# untitled.net
KiCad netlist of a schematic drawn in EAGLE
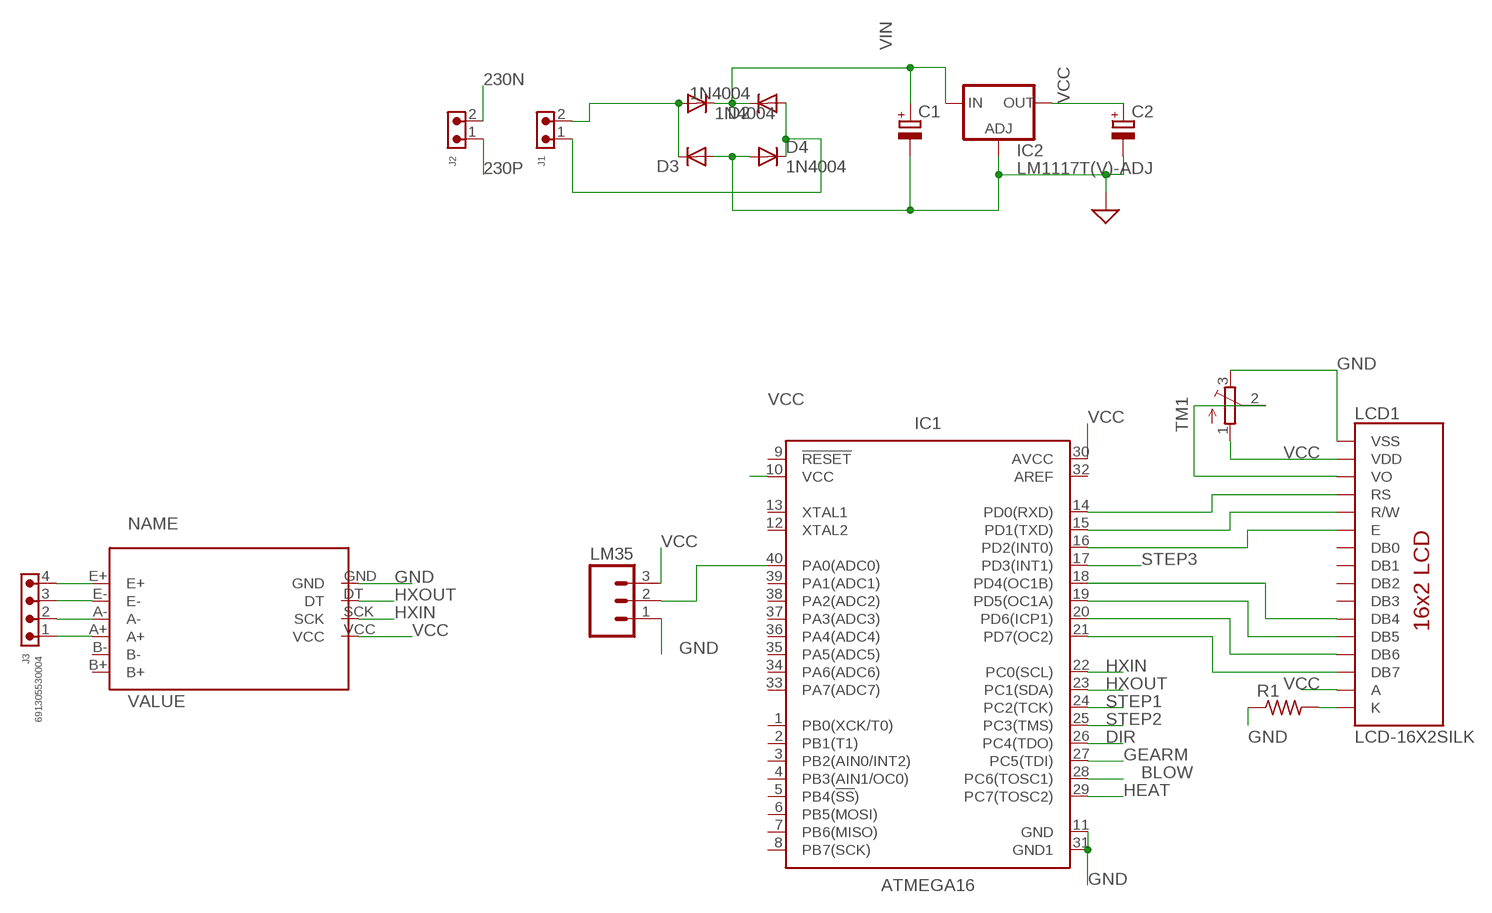
[diagram p0: schematic, sheet 1]

(export (version "E")
  (design (tool "Eeschema 10.0.6"))
  (components
    (comp (ref "C1")
      (value "CPOL-EUE5-10.5")
      (footprint "eagle-import:E5-10,5")
      (libsource (lib "eagle-import") (part "CPOL-EUE5-10.5"))
    )
    (comp (ref "C2")
      (value "CPOL-EUE5-10.5")
      (footprint "eagle-import:E5-10,5")
      (libsource (lib "eagle-import") (part "CPOL-EUE5-10.5"))
    )
    (comp (ref "D1")
      (value "1N4004")
      (footprint "eagle-import:DO41-10")
      (libsource (lib "eagle-import") (part "1N4004"))
    )
    (comp (ref "D2")
      (value "1N4004")
      (footprint "eagle-import:DO41-10")
      (libsource (lib "eagle-import") (part "1N4004"))
    )
    (comp (ref "D3")
      (value "1N4004")
      (footprint "eagle-import:DO41-10")
      (libsource (lib "eagle-import") (part "1N4004"))
    )
    (comp (ref "D4")
      (value "1N4004")
      (footprint "eagle-import:DO41-10")
      (libsource (lib "eagle-import") (part "1N4004"))
    )
    (comp (ref "IC1")
      (value "ATMEGA16")
      (footprint "eagle-import:DIP1587W56P254L5229H482Q40B")
      (fields (field (name "MANUFACTURER") "Microchip Technology") (field (name "MPN") "ATMEGA32-16PU"))
      (libsource (lib "eagle-import") (part "ATMEGA32DIP-16PU_"))
    )
    (comp (ref "IC2")
      (value "LM1117T(V)-ADJ")
      (footprint "eagle-import:TO220V")
      (fields (field (name "MF") "Texas Instruments") (field (name "MPN") "LM1777T-ADJ"))
      (libsource (lib "eagle-import") (part "LM1117?-ADJT(V)"))
    )
    (comp (ref "J1")
      (value "691305530002")
      (footprint "eagle-import:691305530002")
      (libsource (lib "eagle-import") (part "691305530002"))
    )
    (comp (ref "J2")
      (value "691305530002")
      (footprint "eagle-import:691305530002")
      (libsource (lib "eagle-import") (part "691305530002"))
    )
    (comp (ref "J3")
      (value "691305530004")
      (footprint "eagle-import:691305530004")
      (libsource (lib "eagle-import") (part "691305530004"))
    )
    (comp (ref "LCD1")
      (value "LCD-16X2SILK")
      (footprint "eagle-import:LCD-16X2")
      (libsource (lib "eagle-import") (part "LCD-16X2SILK"))
    )
    (comp (ref "LM35")
      (value "M03")
      (footprint "eagle-import:03P")
      (libsource (lib "eagle-import") (part "M03"))
    )
    (comp (ref "R1")
      (value "R-US_0207/9")
      (footprint "eagle-import:0207_9")
      (libsource (lib "eagle-import") (part "R-US_0207/9"))
    )
    (comp (ref "TM1")
      (value "TRIMPOTTC33X")
      (footprint "eagle-import:TC33X")
      (libsource (lib "eagle-import") (part "TRIMPOTTC33X"))
    )
    (comp (ref "U$3")
      (value "HX711A")
      (footprint "eagle-import:HX711")
      (libsource (lib "eagle-import") (part "HX711A"))
    )
  )
  (nets
    (net (code "1") (name "/230N") (class "Default")
      (node (ref "J2") (pin "2") (pinfunction "2_2") (pintype "passive"))
    )
    (net (code "2") (name "/230P") (class "Default")
      (node (ref "J2") (pin "1") (pinfunction "1_1") (pintype "passive"))
    )
    (net (code "3") (name "/BLOW") (class "Default")
      (node (ref "IC1") (pin "28") (pinfunction "PC6(TOSC1)_28") (pintype "bidirectional"))
    )
    (net (code "4") (name "/DIR") (class "Default")
      (node (ref "IC1") (pin "26") (pinfunction "PC4(TDO)_26") (pintype "output"))
    )
    (net (code "5") (name "/GEARM") (class "Default")
      (node (ref "IC1") (pin "27") (pinfunction "PC5(TDI)_27") (pintype "input"))
    )
    (net (code "6") (name "/HEAT") (class "Default")
      (node (ref "IC1") (pin "29") (pinfunction "PC7(TOSC2)_29") (pintype "bidirectional"))
    )
    (net (code "7") (name "/HXIN") (class "Default")
      (node (ref "IC1") (pin "22") (pinfunction "PC0(SCL)_22") (pintype "bidirectional"))
      (node (ref "U$3") (pin "SCK") (pinfunction "SCK_SCK") (pintype "bidirectional"))
    )
    (net (code "8") (name "/HXOUT") (class "Default")
      (node (ref "IC1") (pin "23") (pinfunction "PC1(SDA)_23") (pintype "bidirectional"))
      (node (ref "U$3") (pin "DT") (pinfunction "DT_DT") (pintype "bidirectional"))
    )
    (net (code "9") (name "/STEP1") (class "Default")
      (node (ref "IC1") (pin "24") (pinfunction "PC2(TCK)_24") (pintype "input"))
    )
    (net (code "10") (name "/STEP2") (class "Default")
      (node (ref "IC1") (pin "25") (pinfunction "PC3(TMS)_25") (pintype "input"))
    )
    (net (code "11") (name "/STEP3") (class "Default")
      (node (ref "IC1") (pin "17") (pinfunction "PD3(INT1)_17") (pintype "bidirectional"))
    )
    (net (code "12") (name "/VCC") (class "Default")
      (node (ref "C2") (pin "+") (pinfunction "+_+") (pintype "passive"))
      (node (ref "IC1") (pin "10") (pinfunction "VCC_10") (pintype "power_in"))
      (node (ref "IC1") (pin "30") (pinfunction "AVCC_30") (pintype "power_in"))
      (node (ref "IC2") (pin "2") (pinfunction "OUT_2") (pintype "passive"))
      (node (ref "LCD1") (pin "15") (pinfunction "A_15") (pintype "power_in"))
      (node (ref "LCD1") (pin "2") (pinfunction "VDD_2") (pintype "power_in"))
      (node (ref "LM35") (pin "3") (pinfunction "3_3") (pintype "passive"))
      (node (ref "TM1") (pin "1") (pinfunction "A_1") (pintype "passive"))
      (node (ref "U$3") (pin "VCC") (pinfunction "VCC_VCC") (pintype "bidirectional"))
    )
    (net (code "13") (name "/VIN") (class "Default")
      (node (ref "C1") (pin "+") (pinfunction "+_+") (pintype "passive"))
      (node (ref "D1") (pin "C") (pinfunction "C_C") (pintype "passive"))
      (node (ref "D2") (pin "C") (pinfunction "C_C") (pintype "passive"))
      (node (ref "IC2") (pin "3") (pinfunction "IN_3") (pintype "input"))
    )
    (net (code "14") (name "Net-(D1-PadA)") (class "Default")
      (node (ref "D1") (pin "A") (pinfunction "A_A") (pintype "passive"))
      (node (ref "D3") (pin "C") (pinfunction "C_C") (pintype "passive"))
      (node (ref "J1") (pin "2") (pinfunction "2_2") (pintype "passive"))
    )
    (net (code "15") (name "Net-(D2-PadA)") (class "Default")
      (node (ref "D2") (pin "A") (pinfunction "A_A") (pintype "passive"))
      (node (ref "D4") (pin "C") (pinfunction "C_C") (pintype "passive"))
      (node (ref "J1") (pin "1") (pinfunction "1_1") (pintype "passive"))
    )
    (net (code "16") (name "Net-(IC1-PA0(ADC0))") (class "Default")
      (node (ref "IC1") (pin "40") (pinfunction "PA0(ADC0)_40") (pintype "bidirectional"))
      (node (ref "LM35") (pin "2") (pinfunction "2_2") (pintype "passive"))
    )
    (net (code "17") (name "Net-(IC1-PD0(RXD))") (class "Default")
      (node (ref "IC1") (pin "14") (pinfunction "PD0(RXD)_14") (pintype "bidirectional"))
      (node (ref "LCD1") (pin "4") (pinfunction "RS_4") (pintype "input"))
    )
    (net (code "18") (name "Net-(IC1-PD1(TXD))") (class "Default")
      (node (ref "IC1") (pin "15") (pinfunction "PD1(TXD)_15") (pintype "bidirectional"))
      (node (ref "LCD1") (pin "5") (pinfunction "R/W_5") (pintype "input"))
    )
    (net (code "19") (name "Net-(IC1-PD2(INT0))") (class "Default")
      (node (ref "IC1") (pin "16") (pinfunction "PD2(INT0)_16") (pintype "bidirectional"))
      (node (ref "LCD1") (pin "6") (pinfunction "E_6") (pintype "input"))
    )
    (net (code "20") (name "Net-(IC1-PD4(OC1B))") (class "Default")
      (node (ref "IC1") (pin "18") (pinfunction "PD4(OC1B)_18") (pintype "bidirectional"))
      (node (ref "LCD1") (pin "11") (pinfunction "DB4_11") (pintype "bidirectional"))
    )
    (net (code "21") (name "Net-(IC1-PD5(OC1A))") (class "Default")
      (node (ref "IC1") (pin "19") (pinfunction "PD5(OC1A)_19") (pintype "bidirectional"))
      (node (ref "LCD1") (pin "12") (pinfunction "DB5_12") (pintype "bidirectional"))
    )
    (net (code "22") (name "Net-(IC1-PD6(ICP1))") (class "Default")
      (node (ref "IC1") (pin "20") (pinfunction "PD6(ICP1)_20") (pintype "bidirectional"))
      (node (ref "LCD1") (pin "13") (pinfunction "DB6_13") (pintype "bidirectional"))
    )
    (net (code "23") (name "Net-(IC1-PD7(OC2))") (class "Default")
      (node (ref "IC1") (pin "21") (pinfunction "PD7(OC2)_21") (pintype "bidirectional"))
      (node (ref "LCD1") (pin "14") (pinfunction "DB7_14") (pintype "bidirectional"))
    )
    (net (code "24") (name "Net-(J3-Pad1)") (class "Default")
      (node (ref "J3") (pin "1") (pinfunction "1_1") (pintype "passive"))
      (node (ref "U$3") (pin "A+") (pinfunction "A+_A+") (pintype "bidirectional"))
    )
    (net (code "25") (name "Net-(J3-Pad2)") (class "Default")
      (node (ref "J3") (pin "2") (pinfunction "2_2") (pintype "passive"))
      (node (ref "U$3") (pin "A-") (pinfunction "A-_A-") (pintype "bidirectional"))
    )
    (net (code "26") (name "Net-(J3-Pad3)") (class "Default")
      (node (ref "J3") (pin "3") (pinfunction "3_3") (pintype "passive"))
      (node (ref "U$3") (pin "E-") (pinfunction "E-_E-") (pintype "bidirectional"))
    )
    (net (code "27") (name "Net-(J3-Pad4)") (class "Default")
      (node (ref "J3") (pin "4") (pinfunction "4_4") (pintype "passive"))
      (node (ref "U$3") (pin "E+") (pinfunction "E+_E+") (pintype "bidirectional"))
    )
    (net (code "28") (name "Net-(LCD1-K)") (class "Default")
      (node (ref "LCD1") (pin "16") (pinfunction "K_16") (pintype "power_in"))
      (node (ref "R1") (pin "2") (pinfunction "2_2") (pintype "passive"))
    )
    (net (code "29") (name "Net-(LCD1-VO)") (class "Default")
      (node (ref "LCD1") (pin "3") (pinfunction "VO_3") (pintype "bidirectional"))
      (node (ref "TM1") (pin "2") (pinfunction "S_2") (pintype "passive"))
    )
    (net (code "30") (name "SUP") (class "Default")
      (node (ref "C1") (pin "-") (pinfunction "-_-") (pintype "passive"))
      (node (ref "C2") (pin "-") (pinfunction "-_-") (pintype "passive"))
      (node (ref "D3") (pin "A") (pinfunction "A_A") (pintype "passive"))
      (node (ref "D4") (pin "A") (pinfunction "A_A") (pintype "passive"))
      (node (ref "IC1") (pin "11") (pinfunction "GND_11") (pintype "power_in"))
      (node (ref "IC1") (pin "31") (pinfunction "GND1_31") (pintype "power_in"))
      (node (ref "IC2") (pin "1") (pinfunction "ADJ_1") (pintype "input"))
      (node (ref "LCD1") (pin "1") (pinfunction "VSS_1") (pintype "power_in"))
      (node (ref "LM35") (pin "1") (pinfunction "1_1") (pintype "passive"))
      (node (ref "R1") (pin "1") (pinfunction "1_1") (pintype "passive"))
      (node (ref "TM1") (pin "3") (pinfunction "E_3") (pintype "passive"))
      (node (ref "U$3") (pin "GND") (pinfunction "GND_GND") (pintype "bidirectional"))
    )
    (net (code "31") (name "unconnected-(IC1-AREF-Pad32)") (class "Default")
      (node (ref "IC1") (pin "32") (pinfunction "AREF_32") (pintype "passive"))
    )
    (net (code "32") (name "unconnected-(IC1-PA1(ADC1)-Pad39)") (class "Default")
      (node (ref "IC1") (pin "39") (pinfunction "PA1(ADC1)_39") (pintype "bidirectional"))
    )
    (net (code "33") (name "unconnected-(IC1-PA2(ADC2)-Pad38)") (class "Default")
      (node (ref "IC1") (pin "38") (pinfunction "PA2(ADC2)_38") (pintype "bidirectional"))
    )
    (net (code "34") (name "unconnected-(IC1-PA3(ADC3)-Pad37)") (class "Default")
      (node (ref "IC1") (pin "37") (pinfunction "PA3(ADC3)_37") (pintype "bidirectional"))
    )
    (net (code "35") (name "unconnected-(IC1-PA4(ADC4)-Pad36)") (class "Default")
      (node (ref "IC1") (pin "36") (pinfunction "PA4(ADC4)_36") (pintype "bidirectional"))
    )
    (net (code "36") (name "unconnected-(IC1-PA5(ADC5)-Pad35)") (class "Default")
      (node (ref "IC1") (pin "35") (pinfunction "PA5(ADC5)_35") (pintype "bidirectional"))
    )
    (net (code "37") (name "unconnected-(IC1-PA6(ADC6)-Pad34)") (class "Default")
      (node (ref "IC1") (pin "34") (pinfunction "PA6(ADC6)_34") (pintype "bidirectional"))
    )
    (net (code "38") (name "unconnected-(IC1-PA7(ADC7)-Pad33)") (class "Default")
      (node (ref "IC1") (pin "33") (pinfunction "PA7(ADC7)_33") (pintype "bidirectional"))
    )
    (net (code "39") (name "unconnected-(IC1-PB0(XCK{slash}T0)-Pad1)") (class "Default")
      (node (ref "IC1") (pin "1") (pinfunction "PB0(XCK/T0)_1") (pintype "bidirectional"))
    )
    (net (code "40") (name "unconnected-(IC1-PB1(T1)-Pad2)") (class "Default")
      (node (ref "IC1") (pin "2") (pinfunction "PB1(T1)_2") (pintype "bidirectional"))
    )
    (net (code "41") (name "unconnected-(IC1-PB2(AIN0{slash}INT2)-Pad3)") (class "Default")
      (node (ref "IC1") (pin "3") (pinfunction "PB2(AIN0/INT2)_3") (pintype "bidirectional"))
    )
    (net (code "42") (name "unconnected-(IC1-PB3(AIN1{slash}OC0)-Pad4)") (class "Default")
      (node (ref "IC1") (pin "4") (pinfunction "PB3(AIN1/OC0)_4") (pintype "bidirectional"))
    )
    (net (code "43") (name "unconnected-(IC1-PB4(~{SS})-Pad5)") (class "Default")
      (node (ref "IC1") (pin "5") (pinfunction "PB4(~{SS})_5") (pintype "bidirectional"))
    )
    (net (code "44") (name "unconnected-(IC1-PB5(MOSI)-Pad6)") (class "Default")
      (node (ref "IC1") (pin "6") (pinfunction "PB5(MOSI)_6") (pintype "bidirectional"))
    )
    (net (code "45") (name "unconnected-(IC1-PB6(MISO)-Pad7)") (class "Default")
      (node (ref "IC1") (pin "7") (pinfunction "PB6(MISO)_7") (pintype "bidirectional"))
    )
    (net (code "46") (name "unconnected-(IC1-PB7(SCK)-Pad8)") (class "Default")
      (node (ref "IC1") (pin "8") (pinfunction "PB7(SCK)_8") (pintype "bidirectional"))
    )
    (net (code "47") (name "unconnected-(IC1-XTAL1-Pad13)") (class "Default")
      (node (ref "IC1") (pin "13") (pinfunction "XTAL1_13") (pintype "passive"))
    )
    (net (code "48") (name "unconnected-(IC1-XTAL2-Pad12)") (class "Default")
      (node (ref "IC1") (pin "12") (pinfunction "XTAL2_12") (pintype "passive"))
    )
    (net (code "49") (name "unconnected-(IC1-~{RESET}-Pad9)") (class "Default")
      (node (ref "IC1") (pin "9") (pinfunction "~{RESET}_9") (pintype "input"))
    )
    (net (code "50") (name "unconnected-(LCD1-DB0-Pad7)") (class "Default")
      (node (ref "LCD1") (pin "7") (pinfunction "DB0_7") (pintype "bidirectional"))
    )
    (net (code "51") (name "unconnected-(LCD1-DB1-Pad8)") (class "Default")
      (node (ref "LCD1") (pin "8") (pinfunction "DB1_8") (pintype "bidirectional"))
    )
    (net (code "52") (name "unconnected-(LCD1-DB2-Pad9)") (class "Default")
      (node (ref "LCD1") (pin "9") (pinfunction "DB2_9") (pintype "bidirectional"))
    )
    (net (code "53") (name "unconnected-(LCD1-DB3-Pad10)") (class "Default")
      (node (ref "LCD1") (pin "10") (pinfunction "DB3_10") (pintype "bidirectional"))
    )
    (net (code "54") (name "unconnected-(U$3-PadB+)") (class "Default")
      (node (ref "U$3") (pin "B+") (pinfunction "B+_B+") (pintype "bidirectional"))
    )
    (net (code "55") (name "unconnected-(U$3-PadB-)") (class "Default")
      (node (ref "U$3") (pin "B-") (pinfunction "B-_B-") (pintype "bidirectional"))
    )
  )
)
